# AmbaSat-05-ZMOD4410.net
KiCad netlist of a schematic drawn in EAGLE
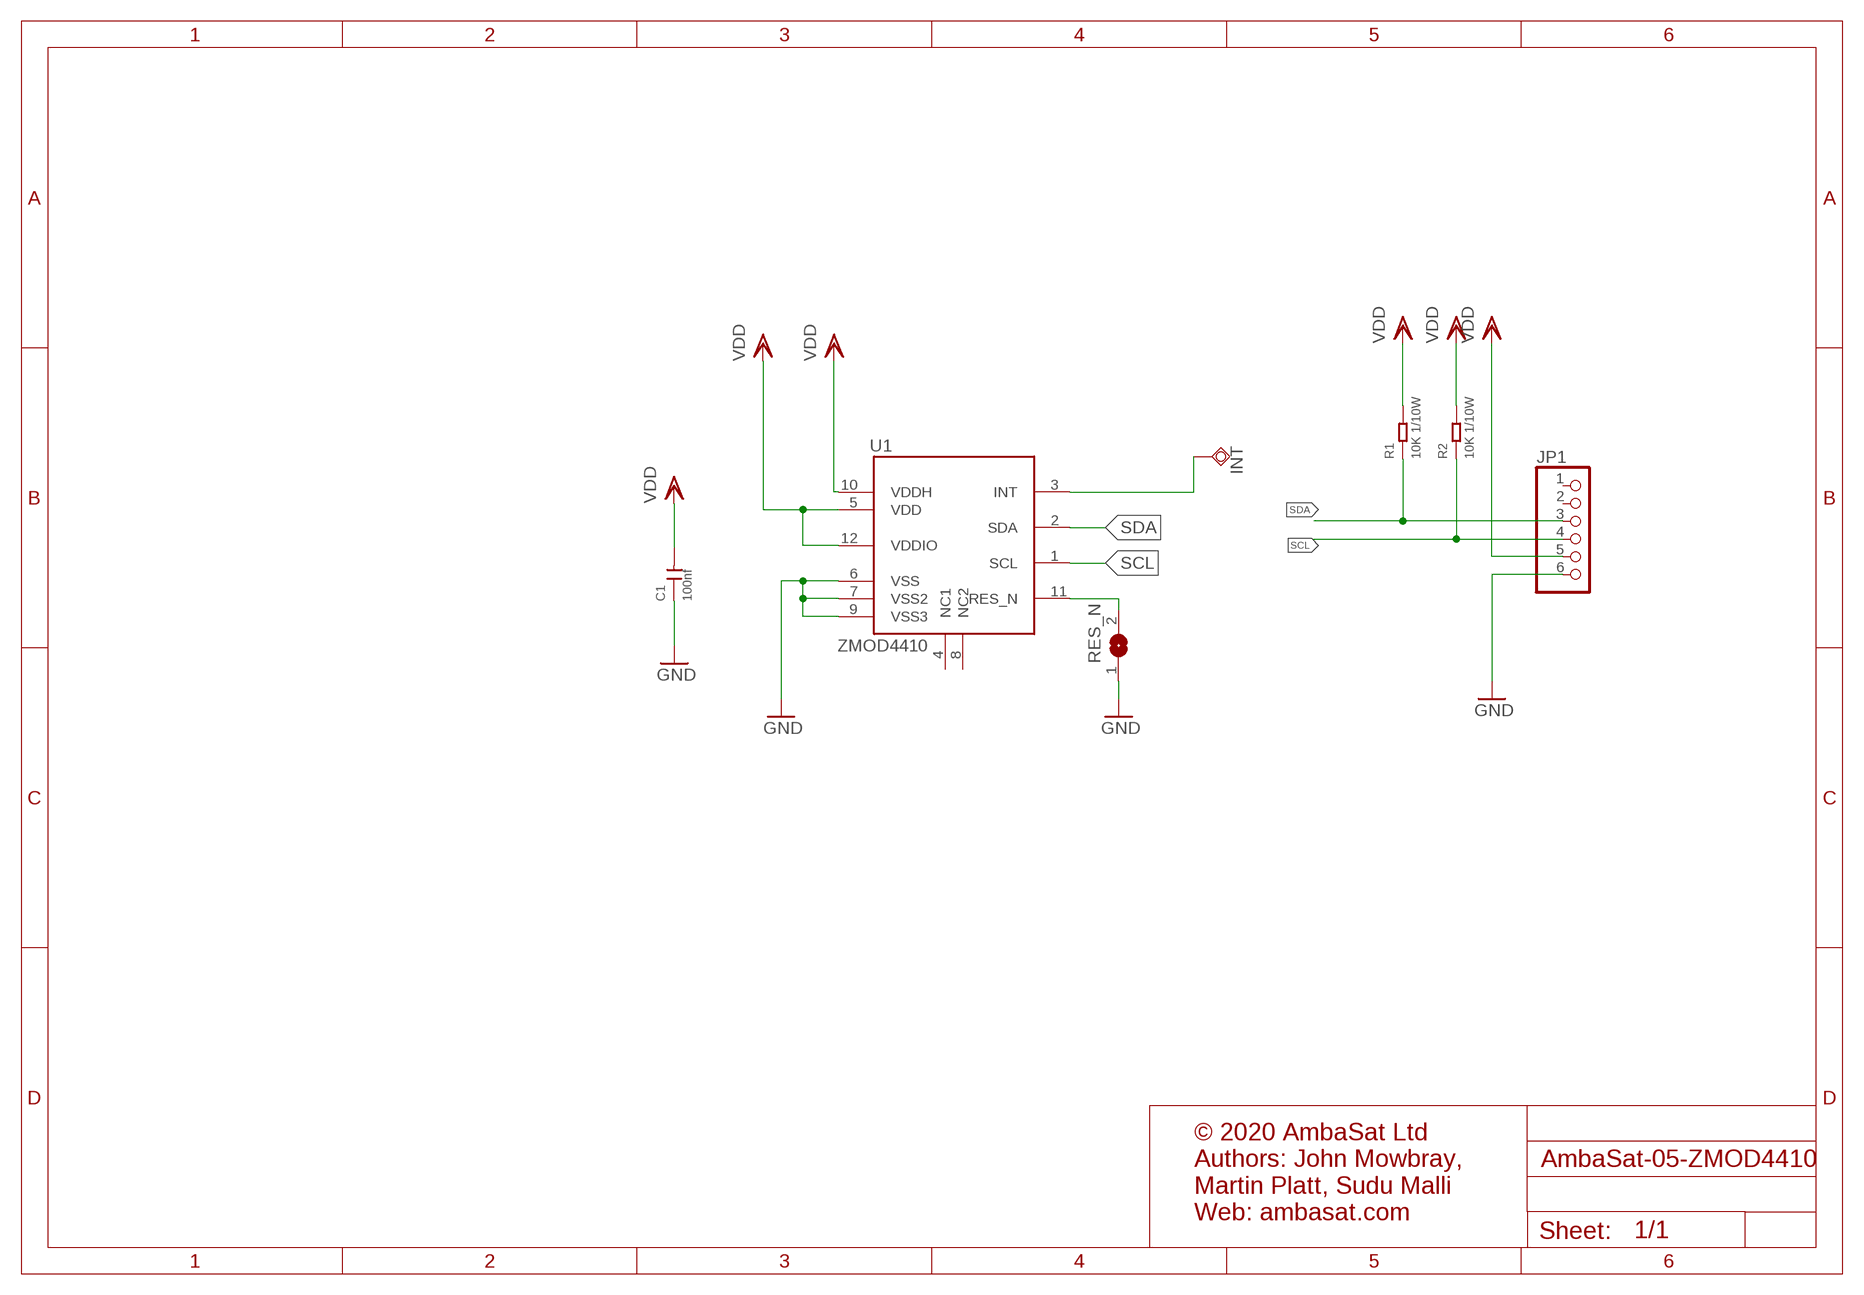
[diagram p0: schematic, sheet 1]

(export (version "E")
  (design (tool "Eeschema 10.0.6"))
  (components
    (comp (ref "C1")
      (value "100nf")
      (footprint "eagle-import:C0603")
      (fields (field (name "MPN") "CC0603KRX7R9BB104"))
      (libsource (lib "eagle-import") (part "CERAMIC-100NF-50V-10%-X7R(0603)"))
    )
    (comp (ref "INT")
      (value "TESTPAD_TPSQTP12R")
      (footprint "eagle-import:TESTPAD_TP12R")
      (libsource (lib "eagle-import") (part "TESTPAD_TPSQTP12R"))
    )
    (comp (ref "JP1")
      (value "HEADER-1X6")
      (footprint "eagle-import:1X06_OVAL")
      (libsource (lib "eagle-import") (part "HEADER-1X6"))
    )
    (comp (ref "R1")
      (value "10K 1/10W")
      (footprint "eagle-import:R0603")
      (fields (field (name "MPN") "RC0603JR-0710KL"))
      (libsource (lib "eagle-import") (part "SMD-RES-10K-5%-1/10W(0603)"))
    )
    (comp (ref "R2")
      (value "10K 1/10W")
      (footprint "eagle-import:R0603")
      (fields (field (name "MPN") "RC0603JR-0710KL"))
      (libsource (lib "eagle-import") (part "SMD-RES-10K-5%-1/10W(0603)"))
    )
    (comp (ref "RES_N")
      (value "SJ")
      (footprint "eagle-import:SJ")
      (libsource (lib "eagle-import") (part "SJ"))
    )
    (comp (ref "U1")
      (value "ZMOD4410")
      (footprint "eagle-import:LGG12D1_3X3X0.7_0.5X1")
      (fields
        (field (name "MANUFACTURER") "IDT, Integrated Device Technology Inc")
        (field (name "MPN") "ZMOD4410AI1V")
      )
      (libsource (lib "eagle-import") (part "ZMOD4410"))
    )
  )
  (nets
    (net (code "1") (name "GND") (class "Default")
      (node (ref "C1") (pin "1") (pinfunction "1_1") (pintype "passive"))
      (node (ref "JP1") (pin "6") (pinfunction "6_6") (pintype "passive"))
      (node (ref "RES_N") (pin "1") (pinfunction "1_1") (pintype "passive"))
      (node (ref "U1") (pin "6") (pinfunction "VSS_6") (pintype "power_in"))
      (node (ref "U1") (pin "7") (pinfunction "VSS2_7") (pintype "bidirectional"))
      (node (ref "U1") (pin "9") (pinfunction "VSS3_9") (pintype "bidirectional"))
    )
    (net (code "2") (name "Net-(U1-INT)") (class "Default")
      (node (ref "INT") (pin "TP") (pinfunction "TP_TP") (pintype "input"))
      (node (ref "U1") (pin "3") (pinfunction "INT_3") (pintype "bidirectional"))
    )
    (net (code "3") (name "Net-(U1-RES_N)") (class "Default")
      (node (ref "RES_N") (pin "2") (pinfunction "2_2") (pintype "passive"))
      (node (ref "U1") (pin "11") (pinfunction "RES_N_11") (pintype "bidirectional"))
    )
    (net (code "4") (name "SCL") (class "Default")
      (node (ref "JP1") (pin "4") (pinfunction "4_4") (pintype "passive"))
      (node (ref "R2") (pin "1") (pinfunction "1_1") (pintype "passive"))
      (node (ref "U1") (pin "1") (pinfunction "SCL_1") (pintype "input"))
    )
    (net (code "5") (name "SDA") (class "Default")
      (node (ref "JP1") (pin "3") (pinfunction "3_3") (pintype "passive"))
      (node (ref "R1") (pin "1") (pinfunction "1_1") (pintype "passive"))
      (node (ref "U1") (pin "2") (pinfunction "SDA_2") (pintype "bidirectional"))
    )
    (net (code "6") (name "VDD") (class "Default")
      (node (ref "C1") (pin "2") (pinfunction "2_2") (pintype "passive"))
      (node (ref "JP1") (pin "5") (pinfunction "5_5") (pintype "passive"))
      (node (ref "R1") (pin "2") (pinfunction "2_2") (pintype "passive"))
      (node (ref "R2") (pin "2") (pinfunction "2_2") (pintype "passive"))
      (node (ref "U1") (pin "10") (pinfunction "VDDH_10") (pintype "bidirectional"))
      (node (ref "U1") (pin "12") (pinfunction "VDDIO_12") (pintype "power_in"))
      (node (ref "U1") (pin "5") (pinfunction "VDD_5") (pintype "power_in"))
    )
    (net (code "7") (name "unconnected-(JP1-Pad1)") (class "Default")
      (node (ref "JP1") (pin "1") (pinfunction "1_1") (pintype "passive"))
    )
    (net (code "8") (name "unconnected-(JP1-Pad2)") (class "Default")
      (node (ref "JP1") (pin "2") (pinfunction "2_2") (pintype "passive"))
    )
    (net (code "9") (name "unconnected-(U1-NC1-Pad4)") (class "Default")
      (node (ref "U1") (pin "4") (pinfunction "NC1_4") (pintype "bidirectional"))
    )
    (net (code "10") (name "unconnected-(U1-NC2-Pad8)") (class "Default")
      (node (ref "U1") (pin "8") (pinfunction "NC2_8") (pintype "bidirectional"))
    )
  )
)
